# M_B_adapter-rotated.net
KiCad netlist of a schematic drawn in EAGLE
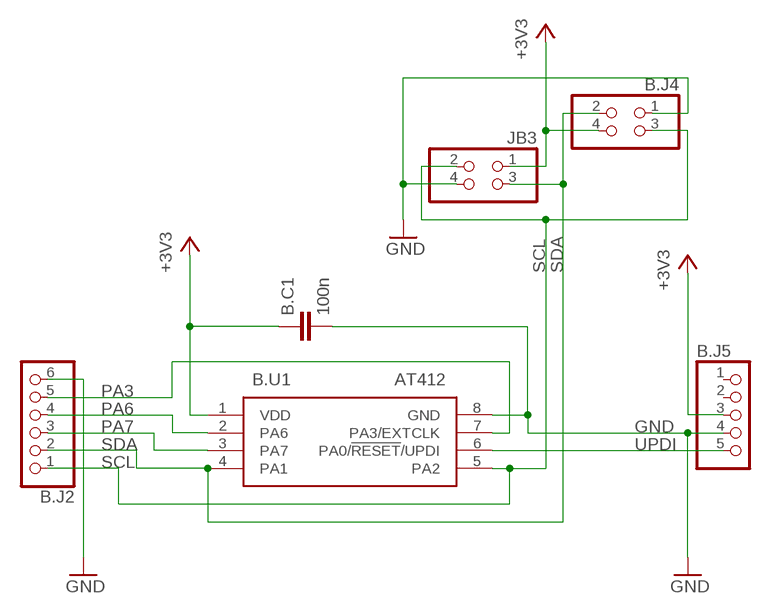
[diagram p0: schematic, sheet 1]

(export (version "E")
  (design (tool "Eeschema 10.0.6"))
  (components
    (comp (ref "B.C1")
      (value "100n")
      (footprint "eagle-import:C0603")
      (libsource (lib "eagle-import") (part "C-EUC0603"))
    )
    (comp (ref "B.J2")
      (value "PINHD-1X6")
      (footprint "eagle-import:1X06")
      (libsource (lib "eagle-import") (part "PINHD-1X6"))
    )
    (comp (ref "B.J4")
      (value "PINHD-2X2")
      (footprint "eagle-import:2X02")
      (libsource (lib "eagle-import") (part "PINHD-2X2"))
    )
    (comp (ref "B.J5")
      (value "PINHD-1X5")
      (footprint "eagle-import:1X05")
      (libsource (lib "eagle-import") (part "PINHD-1X5"))
    )
    (comp (ref "B.U1")
      (value "AT412")
      (footprint "eagle-import:SOIC127P600X175-8N")
      (fields
        (field (name "MANUFACTURER_PART_NUMBER") "ATTINY412-SSN")
        (field (name "MOUSER_PART_NUMBER") "579-ATTINY412-SSN")
      )
      (libsource (lib "eagle-import") (part "ATTINY412-SSN"))
    )
    (comp (ref "JB3")
      (value "PINHD-2X2")
      (footprint "eagle-import:2X02")
      (libsource (lib "eagle-import") (part "PINHD-2X2"))
    )
  )
  (nets
    (net (code "1") (name "+3V3") (class "Default")
      (node (ref "B.C1") (pin "1") (pinfunction "1_1") (pintype "passive"))
      (node (ref "B.J4") (pin "4") (pinfunction "4_4") (pintype "passive"))
      (node (ref "B.J5") (pin "3") (pinfunction "3_3") (pintype "passive"))
      (node (ref "B.U1") (pin "1") (pinfunction "VDD_1") (pintype "bidirectional"))
      (node (ref "JB3") (pin "1") (pinfunction "1_1") (pintype "passive"))
    )
    (net (code "2") (name "/PA3") (class "Default")
      (node (ref "B.J2") (pin "5") (pinfunction "5_5") (pintype "passive"))
      (node (ref "B.U1") (pin "7") (pinfunction "PA3/EXTCLK_7") (pintype "bidirectional"))
    )
    (net (code "3") (name "/PA6") (class "Default")
      (node (ref "B.J2") (pin "4") (pinfunction "4_4") (pintype "passive"))
      (node (ref "B.U1") (pin "2") (pinfunction "PA6_2") (pintype "bidirectional"))
    )
    (net (code "4") (name "/PA7") (class "Default")
      (node (ref "B.J2") (pin "3") (pinfunction "3_3") (pintype "passive"))
      (node (ref "B.U1") (pin "3") (pinfunction "PA7_3") (pintype "bidirectional"))
    )
    (net (code "5") (name "/SCL") (class "Default")
      (node (ref "B.J2") (pin "1") (pinfunction "1_1") (pintype "passive"))
      (node (ref "B.J4") (pin "3") (pinfunction "3_3") (pintype "passive"))
      (node (ref "B.U1") (pin "5") (pinfunction "PA2_5") (pintype "bidirectional"))
      (node (ref "JB3") (pin "2") (pinfunction "2_2") (pintype "passive"))
    )
    (net (code "6") (name "/SDA") (class "Default")
      (node (ref "B.J2") (pin "2") (pinfunction "2_2") (pintype "passive"))
      (node (ref "B.J4") (pin "2") (pinfunction "2_2") (pintype "passive"))
      (node (ref "B.U1") (pin "4") (pinfunction "PA1_4") (pintype "bidirectional"))
      (node (ref "JB3") (pin "3") (pinfunction "3_3") (pintype "passive"))
    )
    (net (code "7") (name "/UPDI") (class "Default")
      (node (ref "B.J5") (pin "5") (pinfunction "5_5") (pintype "passive"))
      (node (ref "B.U1") (pin "6") (pinfunction "PA0/~{RESET}/UPDI_6") (pintype "bidirectional"))
    )
    (net (code "8") (name "GND") (class "Default")
      (node (ref "B.C1") (pin "2") (pinfunction "2_2") (pintype "passive"))
      (node (ref "B.J2") (pin "6") (pinfunction "6_6") (pintype "passive"))
      (node (ref "B.J4") (pin "1") (pinfunction "1_1") (pintype "passive"))
      (node (ref "B.J5") (pin "4") (pinfunction "4_4") (pintype "passive"))
      (node (ref "B.U1") (pin "8") (pinfunction "GND_8") (pintype "bidirectional"))
      (node (ref "JB3") (pin "4") (pinfunction "4_4") (pintype "passive"))
    )
    (net (code "9") (name "unconnected-(B.J5-Pad1)") (class "Default")
      (node (ref "B.J5") (pin "1") (pinfunction "1_1") (pintype "passive"))
    )
    (net (code "10") (name "unconnected-(B.J5-Pad2)") (class "Default")
      (node (ref "B.J5") (pin "2") (pinfunction "2_2") (pintype "passive"))
    )
  )
)
